# DoorCard_ReceiverController.net
KiCad netlist of a schematic drawn in Altium Designer
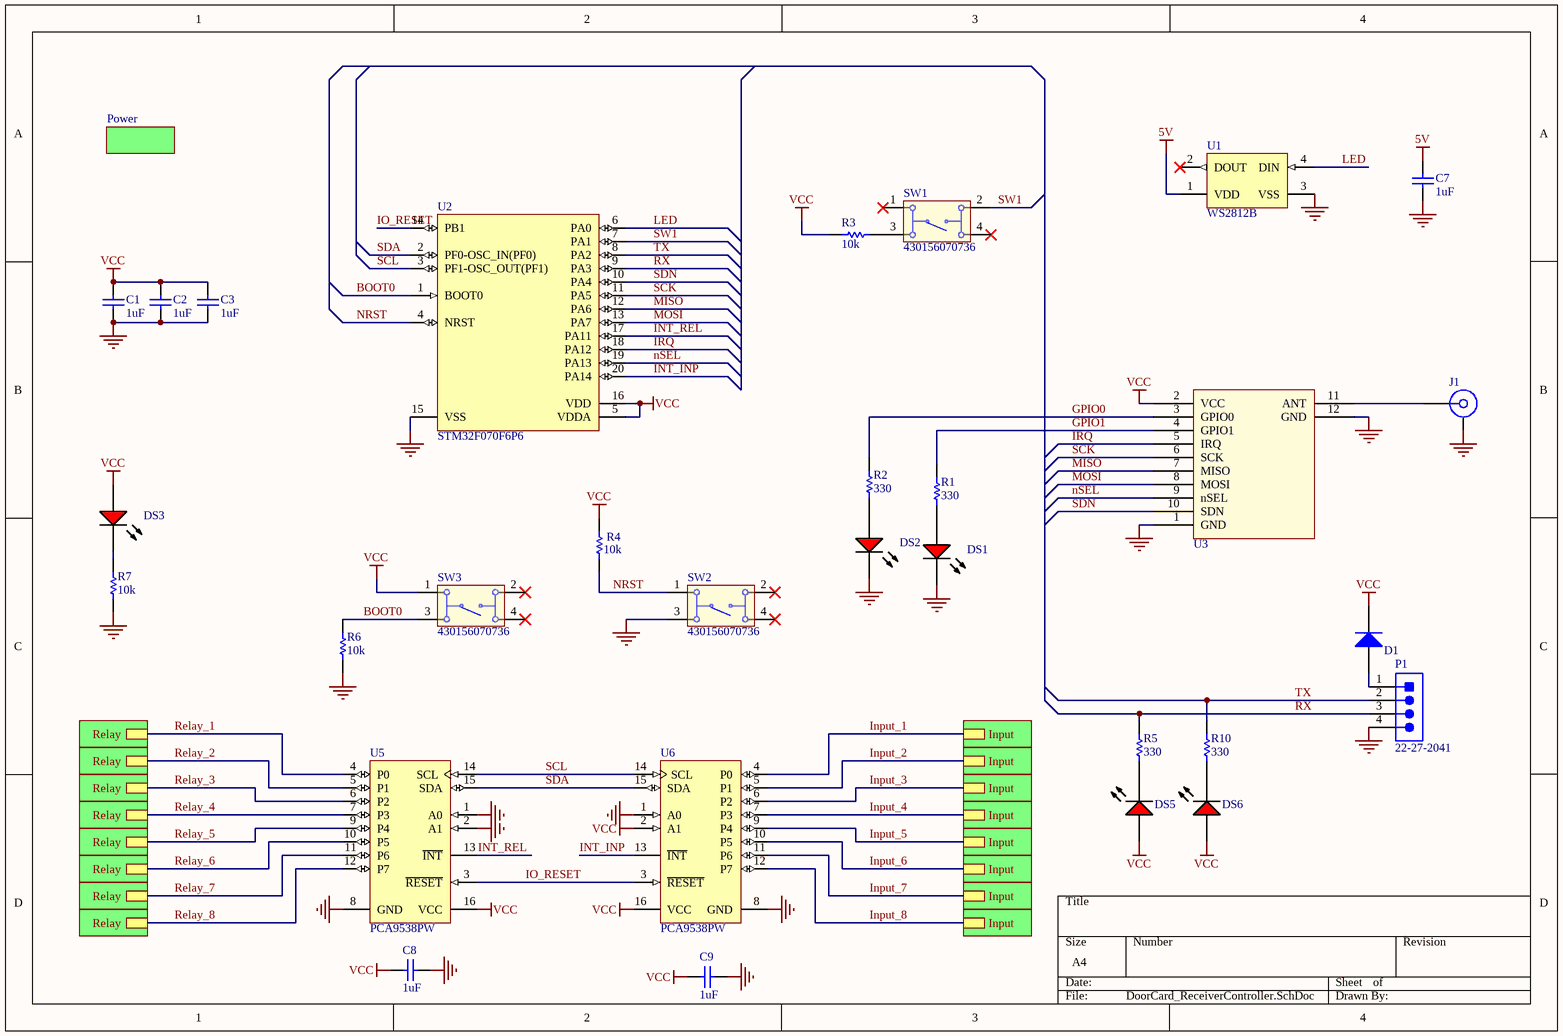
[diagram p0: DoorCard_ReceiverController.SchDoc]

(export (version "E")
  (design (tool "Eeschema 10.0.6"))
  (components
    (comp (ref "C1")
      (value "1uF")
      (footprint "CAPC0805(2012)100_M")
      (description "CAP 1uF 25V ±10% 0805 (2012 Metric) Thickness 1mm SMD")
      (fields (field (name "TOLERANCE") "Â±10%"))
      (libsource (lib "Altium Content Vault") (part "CAP"))
    )
    (comp (ref "C2")
      (value "1uF")
      (footprint "CAPC0805(2012)100_M")
      (description "CAP 1uF 25V ±10% 0805 (2012 Metric) Thickness 1mm SMD")
      (fields (field (name "TOLERANCE") "Â±10%"))
      (libsource (lib "Altium Content Vault") (part "CAP"))
    )
    (comp (ref "C3")
      (value "1uF")
      (footprint "CAPC0805(2012)100_M")
      (description "CAP 1uF 25V ±10% 0805 (2012 Metric) Thickness 1mm SMD")
      (fields (field (name "TOLERANCE") "Â±10%"))
      (libsource (lib "Altium Content Vault") (part "CAP"))
    )
    (comp (ref "C7")
      (value "1uF")
      (footprint "CAPC0805(2012)100_M")
      (description "CAP 1uF 25V ±10% 0805 (2012 Metric) Thickness 1mm SMD")
      (fields (field (name "TOLERANCE") "Â±10%"))
      (libsource (lib "Altium Content Vault") (part "CAP"))
    )
    (comp (ref "C8")
      (value "1uF")
      (footprint "CAPC0805(2012)100_M")
      (description "CAP 1uF 25V ±10% 0805 (2012 Metric) Thickness 1mm SMD")
      (fields (field (name "TOLERANCE") "Â±10%"))
      (libsource (lib "Altium Content Vault") (part "CAP"))
    )
    (comp (ref "C9")
      (value "1uF")
      (footprint "CAPC0805(2012)100_M")
      (description "CAP 1uF 25V ±10% 0805 (2012 Metric) Thickness 1mm SMD")
      (fields (field (name "TOLERANCE") "Â±10%"))
      (libsource (lib "Altium Content Vault") (part "CAP"))
    )
    (comp (ref "D1")
      (value "MMSD4148T3G")
      (footprint "ONSC-SOD123-2-425G-04_V")
      (description "Switching Diode, 100 V, 200 mA, -55 to 150 degC, 2-Pin SOD123 (425), RoHS, Tape and Reel")
      (fields (field (name "MANUFACTURER") "ON Semiconductor"))
      (libsource (lib "Altium Content Vault") (part "ONSC-MMSD4148-SOD123-2"))
    )
    (comp (ref "DS1")
      (value "TLMS1100-GS08")
      (footprint "VISH-TLMX1100_V")
      (description "LED, RED, 2.1 V, -40 to 100 degC, 2-Pin SMD (0603), RoHS, Tape and Reel")
      (fields (field (name "TOLERANCE") "5%"))
      (libsource (lib "Altium Content Vault") (part "LED-RED-AK-2"))
    )
    (comp (ref "DS2")
      (value "TLMS1100-GS08")
      (footprint "VISH-TLMX1100_V")
      (description "LED, RED, 2.1 V, -40 to 100 degC, 2-Pin SMD (0603), RoHS, Tape and Reel")
      (fields (field (name "TOLERANCE") "5%"))
      (libsource (lib "Altium Content Vault") (part "LED-RED-AK-2"))
    )
    (comp (ref "DS3")
      (value "TLMS1100-GS08")
      (footprint "VISH-TLMX1100_V")
      (description "LED, RED, 2.1 V, -40 to 100 degC, 2-Pin SMD (0603), RoHS, Tape and Reel")
      (fields (field (name "TOLERANCE") "5%"))
      (libsource (lib "Altium Content Vault") (part "LED-RED-AK-2"))
    )
    (comp (ref "DS5")
      (value "TLMS1100-GS08")
      (footprint "VISH-TLMX1100_V")
      (description "LED, RED, 2.1 V, -40 to 100 degC, 2-Pin SMD (0603), RoHS, Tape and Reel")
      (fields (field (name "TOLERANCE") "5%"))
      (libsource (lib "Altium Content Vault") (part "LED-RED-AK-2"))
    )
    (comp (ref "DS6")
      (value "TLMS1100-GS08")
      (footprint "VISH-TLMX1100_V")
      (description "LED, RED, 2.1 V, -40 to 100 degC, 2-Pin SMD (0603), RoHS, Tape and Reel")
      (fields (field (name "TOLERANCE") "5%"))
      (libsource (lib "Altium Content Vault") (part "LED-RED-AK-2"))
    )
    (comp (ref "J1")
      (value "32K145-400L5")
      (footprint "ROS-32K145-400L5_V")
      (description "SMA Right Angle Jack, Edge Mount, Up to 18 GHz, -55 to 155 degC")
      (fields (field (name "MANUFACTURER") "Rosenberger"))
      (libsource (lib "Altium Content Vault") (part "ROS-CN-1F-RF1-A"))
    )
    (comp (ref "P1")
      (value "22-27-2041")
      (footprint "MOLX-22-27-2041_V")
      (description "Male Header, Pitch 2.54 mm, 1 x 4 Position, Height 11.7 mm, Tail Length 3.56 mm, RoHS, Bulk")
      (fields (field (name "MANUFACTURER") "Molex"))
      (libsource (lib "Altium Content Vault") (part "CN-1P-M-R4"))
    )
    (comp (ref "R1")
      (value "330")
      (footprint "RESC0805(2012)_L")
      (description "10K2 0.125W 1% 0805 (2012 Metric)  SMD")
      (fields (field (name "TOLERANCE") "1 %") (field (name "POWER") "0.125 W"))
      (libsource (lib "Altium Content Vault") (part "RES"))
    )
    (comp (ref "R2")
      (value "330")
      (footprint "RESC0805(2012)_L")
      (description "10K2 0.125W 1% 0805 (2012 Metric)  SMD")
      (fields (field (name "TOLERANCE") "1 %") (field (name "POWER") "0.125 W"))
      (libsource (lib "Altium Content Vault") (part "RES"))
    )
    (comp (ref "R3")
      (value "10k")
      (footprint "RESC0805(2012)_L")
      (description "10K2 0.125W 1% 0805 (2012 Metric)  SMD")
      (fields (field (name "TOLERANCE") "1 %") (field (name "POWER") "0.125 W"))
      (libsource (lib "Altium Content Vault") (part "RES"))
    )
    (comp (ref "R4")
      (value "10k")
      (footprint "RESC0805(2012)_L")
      (description "10K2 0.125W 1% 0805 (2012 Metric)  SMD")
      (fields (field (name "TOLERANCE") "1 %") (field (name "POWER") "0.125 W"))
      (libsource (lib "Altium Content Vault") (part "RES"))
    )
    (comp (ref "R5")
      (value "330")
      (footprint "RESC0805(2012)_L")
      (description "10K2 0.125W 1% 0805 (2012 Metric)  SMD")
      (fields (field (name "TOLERANCE") "1 %") (field (name "POWER") "0.125 W"))
      (libsource (lib "Altium Content Vault") (part "RES"))
    )
    (comp (ref "R6")
      (value "10k")
      (footprint "RESC0805(2012)_L")
      (description "10K2 0.125W 1% 0805 (2012 Metric)  SMD")
      (fields (field (name "TOLERANCE") "1 %") (field (name "POWER") "0.125 W"))
      (libsource (lib "Altium Content Vault") (part "RES"))
    )
    (comp (ref "R7")
      (value "10k")
      (footprint "RESC0805(2012)_L")
      (description "10K2 0.125W 1% 0805 (2012 Metric)  SMD")
      (fields (field (name "TOLERANCE") "1 %") (field (name "POWER") "0.125 W"))
      (libsource (lib "Altium Content Vault") (part "RES"))
    )
    (comp (ref "R10")
      (value "330")
      (footprint "RESC0805(2012)_L")
      (description "10K2 0.125W 1% 0805 (2012 Metric)  SMD")
      (fields (field (name "TOLERANCE") "1 %") (field (name "POWER") "0.125 W"))
      (libsource (lib "Altium Content Vault") (part "RES"))
    )
    (comp (ref "SW1")
      (value "430156070736")
      (footprint "430156070736")
      (description "WS-TATV THT Tact Switch 6X6 mm")
      (fields (field (name "MANUFACTURER") "Wuerth Elektronik"))
      (libsource (lib "Altium Content Vault") (part "WE-TACT-SW-4"))
    )
    (comp (ref "SW2")
      (value "430156070736")
      (footprint "430156070736")
      (description "WS-TATV THT Tact Switch 6X6 mm")
      (fields (field (name "MANUFACTURER") "Wuerth Elektronik"))
      (libsource (lib "Altium Content Vault") (part "WE-TACT-SW-4"))
    )
    (comp (ref "SW3")
      (value "430156070736")
      (footprint "430156070736")
      (description "WS-TATV THT Tact Switch 6X6 mm")
      (fields (field (name "MANUFACTURER") "Wuerth Elektronik"))
      (libsource (lib "Altium Content Vault") (part "WE-TACT-SW-4"))
    )
    (comp (ref "U1")
      (value "WS2812B")
      (footprint "ADAI-WS2812B_V")
      (fields (field (name "TOLERANCE") "10%"))
      (libsource (lib "Altium Content Vault") (part "ADAI-WS2812B-4"))
    )
    (comp (ref "U2")
      (value "STM32F070F6P6")
      (footprint "STM-TSSOP20_M")
      (fields (field (name "MANUFACTURER") "STMicroelectronics"))
      (libsource (lib "Altium Content Vault") (part "MC-ARM-STM32F070-TSSOP20"))
    )
    (comp (ref "U3")
      (value "Si4463")
      (footprint "E10-433MS")
      (description "E10-433MS")
      (libsource (lib "SiliconLabs") (part "Component_1"))
    )
    (comp (ref "U5")
      (value "PCA9538PW")
      (footprint "PW16_N")
      (fields (field (name "MANUFACTURER") "Texas Instruments"))
      (libsource (lib "Altium Content Vault") (part "TI-PCA9538-TSSOP_PW-16"))
    )
    (comp (ref "U6")
      (value "PCA9538PW")
      (footprint "PW16_N")
      (fields (field (name "MANUFACTURER") "Texas Instruments"))
      (libsource (lib "") (part "TI-PCA9538-TSSOP_PW-16_1"))
    )
  )
  (nets
    (net (code "2") (name "/BOOT0") (class "Default")
      (node (ref "R6") (pin "2") (pinfunction "2_2") (pintype "passive"))
      (node (ref "SW3") (pin "3") (pinfunction "3_3") (pintype "passive"))
      (node (ref "U2") (pin "1") (pinfunction "BOOT0_1") (pintype "input"))
    )
    (net (code "3") (name "/GPIO0") (class "Default")
      (node (ref "R2") (pin "1") (pinfunction "1_1") (pintype "passive"))
      (node (ref "U3") (pin "3") (pinfunction "GPIO0_3") (pintype "passive"))
    )
    (net (code "4") (name "/GPIO1") (class "Default")
      (node (ref "R1") (pin "1") (pinfunction "1_1") (pintype "passive"))
      (node (ref "U3") (pin "4") (pinfunction "GPIO1_4") (pintype "passive"))
    )
    (net (code "5") (name "/INT_INP") (class "Default")
      (node (ref "U2") (pin "20") (pinfunction "PA14_20") (pintype "bidirectional"))
      (node (ref "U6") (pin "13") (pinfunction "~{INT}_13") (pintype "open_collector"))
    )
    (net (code "6") (name "/INT_REL") (class "Default")
      (node (ref "U2") (pin "17") (pinfunction "PA11_17") (pintype "bidirectional"))
      (node (ref "U5") (pin "13") (pinfunction "~{INT}_13") (pintype "open_collector"))
    )
    (net (code "7") (name "/IO_RESET") (class "Default")
      (node (ref "U2") (pin "14") (pinfunction "PB1_14") (pintype "bidirectional"))
      (node (ref "U5") (pin "3") (pinfunction "~{RESET}_3") (pintype "input"))
      (node (ref "U6") (pin "3") (pinfunction "~{RESET}_3") (pintype "input"))
    )
    (net (code "8") (name "/IRQ") (class "Default")
      (node (ref "U2") (pin "18") (pinfunction "PA12_18") (pintype "bidirectional"))
      (node (ref "U3") (pin "5") (pinfunction "IRQ_5") (pintype "passive"))
    )
    (net (code "9") (name "/Input_1") (class "Default")
      (node (ref "U6") (pin "4") (pinfunction "P0_4") (pintype "bidirectional"))
    )
    (net (code "10") (name "/Input_2") (class "Default")
      (node (ref "U6") (pin "5") (pinfunction "P1_5") (pintype "bidirectional"))
    )
    (net (code "11") (name "/Input_3") (class "Default")
      (node (ref "U6") (pin "6") (pinfunction "P2_6") (pintype "bidirectional"))
    )
    (net (code "12") (name "/Input_4") (class "Default")
      (node (ref "U6") (pin "7") (pinfunction "P3_7") (pintype "bidirectional"))
    )
    (net (code "13") (name "/Input_5") (class "Default")
      (node (ref "U6") (pin "9") (pinfunction "P4_9") (pintype "bidirectional"))
    )
    (net (code "14") (name "/Input_6") (class "Default")
      (node (ref "U6") (pin "10") (pinfunction "P5_10") (pintype "bidirectional"))
    )
    (net (code "15") (name "/Input_7") (class "Default")
      (node (ref "U6") (pin "11") (pinfunction "P6_11") (pintype "bidirectional"))
    )
    (net (code "16") (name "/Input_8") (class "Default")
      (node (ref "U6") (pin "12") (pinfunction "P7_12") (pintype "bidirectional"))
    )
    (net (code "17") (name "/LED") (class "Default")
      (node (ref "U1") (pin "4") (pinfunction "DIN_4") (pintype "input"))
      (node (ref "U2") (pin "6") (pinfunction "PA0_6") (pintype "bidirectional"))
    )
    (net (code "18") (name "/MISO") (class "Default")
      (node (ref "U2") (pin "12") (pinfunction "PA6_12") (pintype "bidirectional"))
      (node (ref "U3") (pin "7") (pinfunction "MISO_7") (pintype "passive"))
    )
    (net (code "19") (name "/MOSI") (class "Default")
      (node (ref "U2") (pin "13") (pinfunction "PA7_13") (pintype "bidirectional"))
      (node (ref "U3") (pin "8") (pinfunction "MOSI_8") (pintype "passive"))
    )
    (net (code "20") (name "/NRST") (class "Default")
      (node (ref "R4") (pin "1") (pinfunction "1_1") (pintype "passive"))
      (node (ref "SW2") (pin "1") (pinfunction "1_1") (pintype "passive"))
      (node (ref "U2") (pin "4") (pinfunction "NRST_4") (pintype "bidirectional"))
    )
    (net (code "21") (name "/RX") (class "Default")
      (node (ref "P1") (pin "3") (pinfunction "3_3") (pintype "passive"))
      (node (ref "R5") (pin "1") (pinfunction "1_1") (pintype "passive"))
      (node (ref "U2") (pin "9") (pinfunction "PA3_9") (pintype "bidirectional"))
    )
    (net (code "22") (name "/Relay_1") (class "Default")
      (node (ref "U5") (pin "4") (pinfunction "P0_4") (pintype "bidirectional"))
    )
    (net (code "23") (name "/Relay_2") (class "Default")
      (node (ref "U5") (pin "5") (pinfunction "P1_5") (pintype "bidirectional"))
    )
    (net (code "24") (name "/Relay_3") (class "Default")
      (node (ref "U5") (pin "6") (pinfunction "P2_6") (pintype "bidirectional"))
    )
    (net (code "25") (name "/Relay_4") (class "Default")
      (node (ref "U5") (pin "7") (pinfunction "P3_7") (pintype "bidirectional"))
    )
    (net (code "26") (name "/Relay_5") (class "Default")
      (node (ref "U5") (pin "9") (pinfunction "P4_9") (pintype "bidirectional"))
    )
    (net (code "27") (name "/Relay_6") (class "Default")
      (node (ref "U5") (pin "10") (pinfunction "P5_10") (pintype "bidirectional"))
    )
    (net (code "28") (name "/Relay_7") (class "Default")
      (node (ref "U5") (pin "11") (pinfunction "P6_11") (pintype "bidirectional"))
    )
    (net (code "29") (name "/Relay_8") (class "Default")
      (node (ref "U5") (pin "12") (pinfunction "P7_12") (pintype "bidirectional"))
    )
    (net (code "30") (name "/SCK") (class "Default")
      (node (ref "U2") (pin "11") (pinfunction "PA5_11") (pintype "bidirectional"))
      (node (ref "U3") (pin "6") (pinfunction "SCK_6") (pintype "passive"))
    )
    (net (code "31") (name "/SCL") (class "Default")
      (node (ref "U2") (pin "3") (pinfunction "PF1-OSC_OUT(PF1)_3") (pintype "bidirectional"))
      (node (ref "U5") (pin "14") (pinfunction "SCL_14") (pintype "input"))
      (node (ref "U6") (pin "14") (pinfunction "SCL_14") (pintype "input"))
    )
    (net (code "32") (name "/SDA") (class "Default")
      (node (ref "U2") (pin "2") (pinfunction "PF0-OSC_IN(PF0)_2") (pintype "bidirectional"))
      (node (ref "U5") (pin "15") (pinfunction "SDA_15") (pintype "bidirectional"))
      (node (ref "U6") (pin "15") (pinfunction "SDA_15") (pintype "bidirectional"))
    )
    (net (code "33") (name "/SDN") (class "Default")
      (node (ref "U2") (pin "10") (pinfunction "PA4_10") (pintype "bidirectional"))
      (node (ref "U3") (pin "10") (pinfunction "SDN_10") (pintype "passive"))
    )
    (net (code "34") (name "/SW1") (class "Default")
      (node (ref "SW1") (pin "2") (pinfunction "2_2") (pintype "passive"))
      (node (ref "U2") (pin "7") (pinfunction "PA1_7") (pintype "bidirectional"))
    )
    (net (code "35") (name "/TX") (class "Default")
      (node (ref "P1") (pin "2") (pinfunction "2_2") (pintype "passive"))
      (node (ref "R10") (pin "1") (pinfunction "1_1") (pintype "passive"))
      (node (ref "U2") (pin "8") (pinfunction "PA2_8") (pintype "bidirectional"))
    )
    (net (code "36") (name "/nSEL") (class "Default")
      (node (ref "U2") (pin "19") (pinfunction "PA13_19") (pintype "bidirectional"))
      (node (ref "U3") (pin "9") (pinfunction "nSEL_9") (pintype "passive"))
    )
    (net (code "37") (name "5V") (class "Default")
      (node (ref "C7") (pin "2") (pinfunction "2_2") (pintype "passive"))
      (node (ref "U1") (pin "1") (pinfunction "VDD_1") (pintype "power_in"))
    )
    (net (code "38") (name "GND") (class "Default")
      (node (ref "C1") (pin "1") (pinfunction "1_1") (pintype "passive"))
      (node (ref "C2") (pin "1") (pinfunction "1_1") (pintype "passive"))
      (node (ref "C3") (pin "1") (pinfunction "1_1") (pintype "passive"))
      (node (ref "C7") (pin "1") (pinfunction "1_1") (pintype "passive"))
      (node (ref "C8") (pin "1") (pinfunction "1_1") (pintype "passive"))
      (node (ref "C9") (pin "1") (pinfunction "1_1") (pintype "passive"))
      (node (ref "DS1") (pin "2") (pinfunction "K_2") (pintype "passive"))
      (node (ref "DS2") (pin "2") (pinfunction "K_2") (pintype "passive"))
      (node (ref "J1") (pin "MP") (pinfunction "MP_MP") (pintype "passive"))
      (node (ref "P1") (pin "4") (pinfunction "4_4") (pintype "passive"))
      (node (ref "R6") (pin "1") (pinfunction "1_1") (pintype "passive"))
      (node (ref "R7") (pin "1") (pinfunction "1_1") (pintype "passive"))
      (node (ref "SW2") (pin "3") (pinfunction "3_3") (pintype "passive"))
      (node (ref "U1") (pin "3") (pinfunction "VSS_3") (pintype "power_in"))
      (node (ref "U2") (pin "15") (pinfunction "VSS_15") (pintype "power_in"))
      (node (ref "U3") (pin "1") (pinfunction "GND_1") (pintype "passive"))
      (node (ref "U3") (pin "12") (pinfunction "GND_12") (pintype "passive"))
      (node (ref "U5") (pin "1") (pinfunction "A0_1") (pintype "input"))
      (node (ref "U5") (pin "2") (pinfunction "A1_2") (pintype "input"))
      (node (ref "U5") (pin "8") (pinfunction "GND_8") (pintype "power_in"))
      (node (ref "U6") (pin "1") (pinfunction "A0_1") (pintype "input"))
      (node (ref "U6") (pin "8") (pinfunction "GND_8") (pintype "power_in"))
    )
    (net (code "39") (name "Net-(D1-ANODE)") (class "Default")
      (node (ref "D1") (pin "2") (pinfunction "ANODE_2") (pintype "passive"))
      (node (ref "P1") (pin "1") (pinfunction "1_1") (pintype "passive"))
    )
    (net (code "40") (name "Net-(DS1-A)") (class "Default")
      (node (ref "DS1") (pin "1") (pinfunction "A_1") (pintype "passive"))
      (node (ref "R1") (pin "2") (pinfunction "2_2") (pintype "passive"))
    )
    (net (code "41") (name "Net-(DS2-A)") (class "Default")
      (node (ref "DS2") (pin "1") (pinfunction "A_1") (pintype "passive"))
      (node (ref "R2") (pin "2") (pinfunction "2_2") (pintype "passive"))
    )
    (net (code "42") (name "Net-(DS3-K)") (class "Default")
      (node (ref "DS3") (pin "2") (pinfunction "K_2") (pintype "passive"))
      (node (ref "R7") (pin "2") (pinfunction "2_2") (pintype "passive"))
    )
    (net (code "43") (name "Net-(DS5-K)") (class "Default")
      (node (ref "DS5") (pin "2") (pinfunction "K_2") (pintype "passive"))
      (node (ref "R5") (pin "2") (pinfunction "2_2") (pintype "passive"))
    )
    (net (code "44") (name "Net-(DS6-K)") (class "Default")
      (node (ref "DS6") (pin "2") (pinfunction "K_2") (pintype "passive"))
      (node (ref "R10") (pin "2") (pinfunction "2_2") (pintype "passive"))
    )
    (net (code "45") (name "Net-(R3-Pad1)") (class "Default")
      (node (ref "R3") (pin "1") (pinfunction "1_1") (pintype "passive"))
      (node (ref "SW1") (pin "3") (pinfunction "3_3") (pintype "passive"))
    )
    (net (code "46") (name "Net-(U3-ANT)") (class "Default")
      (node (ref "J1") (pin "1") (pinfunction "1_1") (pintype "passive"))
      (node (ref "U3") (pin "11") (pinfunction "ANT_11") (pintype "passive"))
    )
    (net (code "47") (name "VCC") (class "Default")
      (node (ref "C1") (pin "2") (pinfunction "2_2") (pintype "passive"))
      (node (ref "C2") (pin "2") (pinfunction "2_2") (pintype "passive"))
      (node (ref "C3") (pin "2") (pinfunction "2_2") (pintype "passive"))
      (node (ref "C8") (pin "2") (pinfunction "2_2") (pintype "passive"))
      (node (ref "C9") (pin "2") (pinfunction "2_2") (pintype "passive"))
      (node (ref "D1") (pin "1") (pinfunction "CATHODE_1") (pintype "passive"))
      (node (ref "DS3") (pin "1") (pinfunction "A_1") (pintype "passive"))
      (node (ref "DS5") (pin "1") (pinfunction "A_1") (pintype "passive"))
      (node (ref "DS6") (pin "1") (pinfunction "A_1") (pintype "passive"))
      (node (ref "R3") (pin "2") (pinfunction "2_2") (pintype "passive"))
      (node (ref "R4") (pin "2") (pinfunction "2_2") (pintype "passive"))
      (node (ref "SW3") (pin "1") (pinfunction "1_1") (pintype "passive"))
      (node (ref "U2") (pin "16") (pinfunction "VDD_16") (pintype "power_in"))
      (node (ref "U2") (pin "5") (pinfunction "VDDA_5") (pintype "power_in"))
      (node (ref "U3") (pin "2") (pinfunction "VCC_2") (pintype "passive"))
      (node (ref "U5") (pin "16") (pinfunction "VCC_16") (pintype "power_in"))
      (node (ref "U6") (pin "16") (pinfunction "VCC_16") (pintype "power_in"))
      (node (ref "U6") (pin "2") (pinfunction "A1_2") (pintype "input"))
    )
    (net (code "48") (name "unconnected-(SW1-Pad1)") (class "Default")
      (node (ref "SW1") (pin "1") (pinfunction "1_1") (pintype "passive+no_connect"))
    )
    (net (code "49") (name "unconnected-(SW1-Pad4)") (class "Default")
      (node (ref "SW1") (pin "4") (pinfunction "4_4") (pintype "passive+no_connect"))
    )
    (net (code "50") (name "unconnected-(SW2-Pad2)") (class "Default")
      (node (ref "SW2") (pin "2") (pinfunction "2_2") (pintype "passive+no_connect"))
    )
    (net (code "51") (name "unconnected-(SW2-Pad4)") (class "Default")
      (node (ref "SW2") (pin "4") (pinfunction "4_4") (pintype "passive+no_connect"))
    )
    (net (code "52") (name "unconnected-(SW3-Pad2)") (class "Default")
      (node (ref "SW3") (pin "2") (pinfunction "2_2") (pintype "passive+no_connect"))
    )
    (net (code "53") (name "unconnected-(SW3-Pad4)") (class "Default")
      (node (ref "SW3") (pin "4") (pinfunction "4_4") (pintype "passive+no_connect"))
    )
    (net (code "54") (name "unconnected-(U1-DOUT-Pad2)") (class "Default")
      (node (ref "U1") (pin "2") (pinfunction "DOUT_2") (pintype "output+no_connect"))
    )
  )
)
